# 03_BEEP.net
KiCad netlist of a schematic drawn in Altium Designer
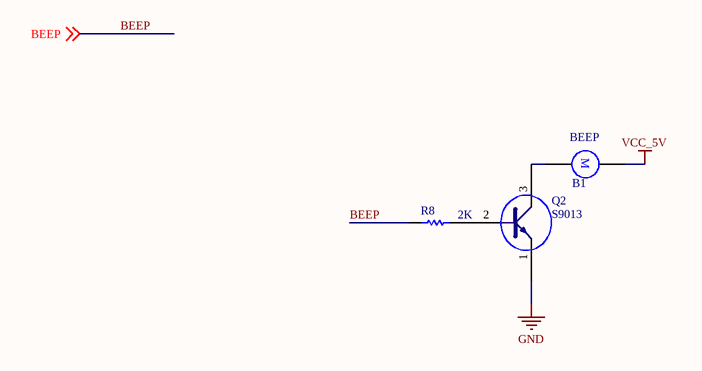
[diagram p0: 03 BEEP.SchDoc]

(export (version "E")
  (design (tool "Eeschema 10.0.6"))
  (components
    (comp (ref "B1")
      (value "BEEP")
      (footprint "Beep")
      (description "Motor, General Kind")
      (fields (field (name "MANUFACTURER") "Generic Components"))
      (libsource (lib "Miscellaneous Devices") (part "Motor"))
    )
    (comp (ref "Q2") (value "S9013") (footprint "PNP-SOT-23") (libsource (lib "专业原理图开发总库") (part "S9013")))
    (comp (ref "R8")
      (value "2K")
      (footprint "R0603")
      (description "Resistor")
      (fields
        (field (name "MANUFACTURER") "Generic Components")
        (field (name "PUBLISHER") "Altium Hobart Technology Centre")
      )
      (libsource (lib "Miscellaneous Devices") (part "Res1"))
    )
  )
  (nets
    (net (code "1") (name "BEEP") (class "Default")
      (node (ref "R8") (pin "1") (pinfunction "1_1") (pintype "passive"))
    )
    (net (code "2") (name "GND") (class "Default") (node (ref "Q2") (pin "1") (pintype "passive")))
    (net (code "3") (name "Net-(B1-Pad2)") (class "Default")
      (node (ref "B1") (pin "2") (pinfunction "2_2") (pintype "passive"))
      (node (ref "Q2") (pin "3") (pintype "passive"))
    )
    (net (code "4") (name "Net-(Q2-Pad2)") (class "Default")
      (node (ref "Q2") (pin "2") (pintype "passive"))
      (node (ref "R8") (pin "2") (pinfunction "2_2") (pintype "passive"))
    )
    (net (code "5") (name "VCC_5V") (class "Default")
      (node (ref "B1") (pin "1") (pinfunction "1_1") (pintype "passive"))
    )
  )
)
